# imp_rev1.net
KiCad netlist of a schematic drawn in EAGLE
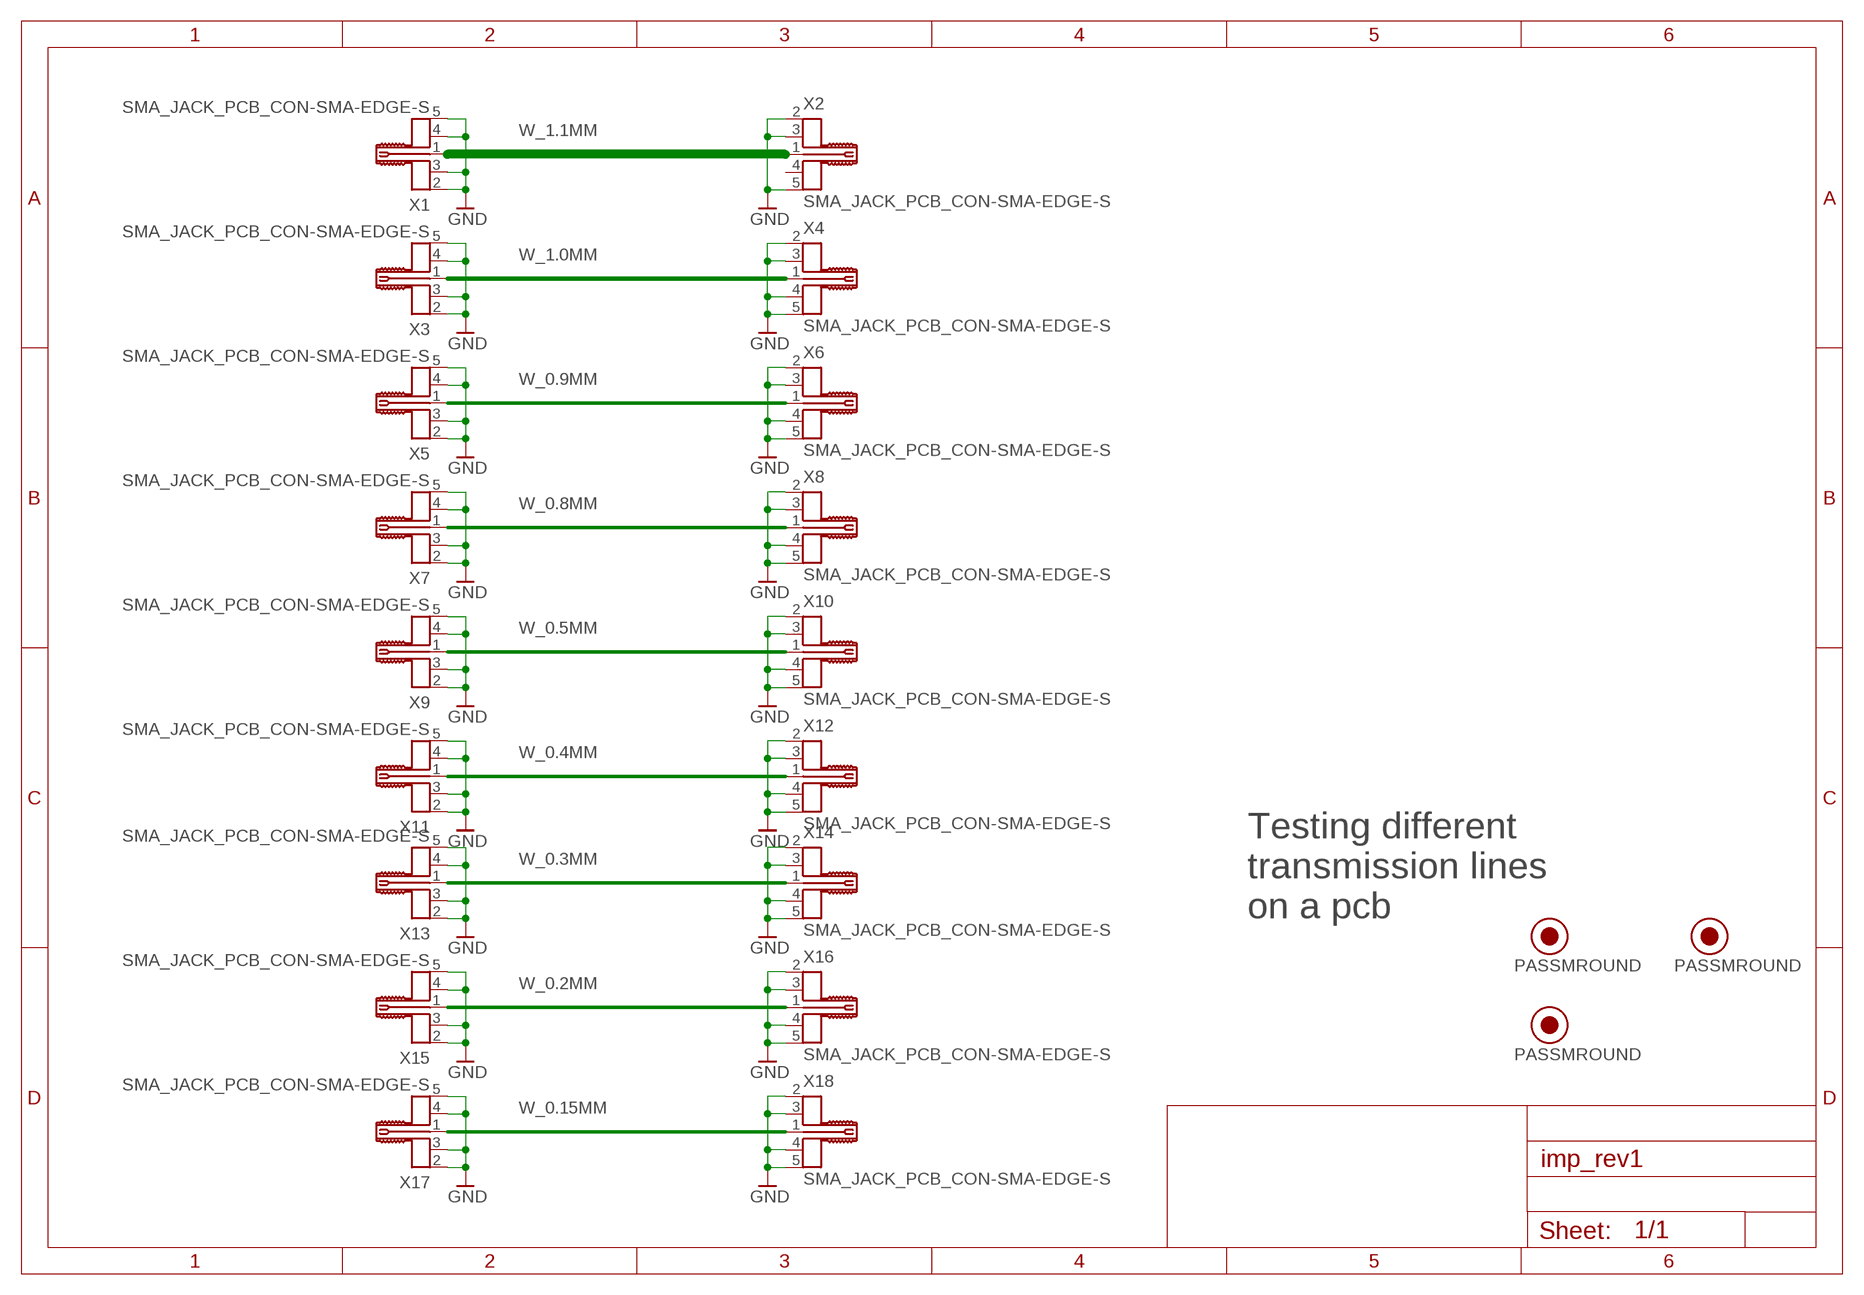
[diagram p0: schematic, sheet 1]

(export (version "E")
  (design (tool "Eeschema 10.0.6"))
  (components
    (comp (ref "P1")
      (value "PASSMROUND")
      (footprint "eagle-import:PASSM")
      (libsource (lib "eagle-import") (part "PASSMROUND"))
    )
    (comp (ref "P2")
      (value "PASSMROUND")
      (footprint "eagle-import:PASSM")
      (libsource (lib "eagle-import") (part "PASSMROUND"))
    )
    (comp (ref "P3")
      (value "PASSMROUND")
      (footprint "eagle-import:PASSM")
      (libsource (lib "eagle-import") (part "PASSMROUND"))
    )
    (comp (ref "X1")
      (value "SMA_JACK_PCB_CON-SMA-EDGE-S")
      (footprint "eagle-import:SMA_JACK_PCB_CON-SMA-EDGE-S")
      (libsource (lib "eagle-import") (part "SMA_JACK_PCB_CON-SMA-EDGE-S"))
    )
    (comp (ref "X2")
      (value "SMA_JACK_PCB_CON-SMA-EDGE-S")
      (footprint "eagle-import:SMA_JACK_PCB_CON-SMA-EDGE-S")
      (libsource (lib "eagle-import") (part "SMA_JACK_PCB_CON-SMA-EDGE-S"))
    )
    (comp (ref "X3")
      (value "SMA_JACK_PCB_CON-SMA-EDGE-S")
      (footprint "eagle-import:SMA_JACK_PCB_CON-SMA-EDGE-S")
      (libsource (lib "eagle-import") (part "SMA_JACK_PCB_CON-SMA-EDGE-S"))
    )
    (comp (ref "X4")
      (value "SMA_JACK_PCB_CON-SMA-EDGE-S")
      (footprint "eagle-import:SMA_JACK_PCB_CON-SMA-EDGE-S")
      (libsource (lib "eagle-import") (part "SMA_JACK_PCB_CON-SMA-EDGE-S"))
    )
    (comp (ref "X5")
      (value "SMA_JACK_PCB_CON-SMA-EDGE-S")
      (footprint "eagle-import:SMA_JACK_PCB_CON-SMA-EDGE-S")
      (libsource (lib "eagle-import") (part "SMA_JACK_PCB_CON-SMA-EDGE-S"))
    )
    (comp (ref "X6")
      (value "SMA_JACK_PCB_CON-SMA-EDGE-S")
      (footprint "eagle-import:SMA_JACK_PCB_CON-SMA-EDGE-S")
      (libsource (lib "eagle-import") (part "SMA_JACK_PCB_CON-SMA-EDGE-S"))
    )
    (comp (ref "X7")
      (value "SMA_JACK_PCB_CON-SMA-EDGE-S")
      (footprint "eagle-import:SMA_JACK_PCB_CON-SMA-EDGE-S")
      (libsource (lib "eagle-import") (part "SMA_JACK_PCB_CON-SMA-EDGE-S"))
    )
    (comp (ref "X8")
      (value "SMA_JACK_PCB_CON-SMA-EDGE-S")
      (footprint "eagle-import:SMA_JACK_PCB_CON-SMA-EDGE-S")
      (libsource (lib "eagle-import") (part "SMA_JACK_PCB_CON-SMA-EDGE-S"))
    )
    (comp (ref "X9")
      (value "SMA_JACK_PCB_CON-SMA-EDGE-S")
      (footprint "eagle-import:SMA_JACK_PCB_CON-SMA-EDGE-S")
      (libsource (lib "eagle-import") (part "SMA_JACK_PCB_CON-SMA-EDGE-S"))
    )
    (comp (ref "X10")
      (value "SMA_JACK_PCB_CON-SMA-EDGE-S")
      (footprint "eagle-import:SMA_JACK_PCB_CON-SMA-EDGE-S")
      (libsource (lib "eagle-import") (part "SMA_JACK_PCB_CON-SMA-EDGE-S"))
    )
    (comp (ref "X11")
      (value "SMA_JACK_PCB_CON-SMA-EDGE-S")
      (footprint "eagle-import:SMA_JACK_PCB_CON-SMA-EDGE-S")
      (libsource (lib "eagle-import") (part "SMA_JACK_PCB_CON-SMA-EDGE-S"))
    )
    (comp (ref "X12")
      (value "SMA_JACK_PCB_CON-SMA-EDGE-S")
      (footprint "eagle-import:SMA_JACK_PCB_CON-SMA-EDGE-S")
      (libsource (lib "eagle-import") (part "SMA_JACK_PCB_CON-SMA-EDGE-S"))
    )
    (comp (ref "X13")
      (value "SMA_JACK_PCB_CON-SMA-EDGE-S")
      (footprint "eagle-import:SMA_JACK_PCB_CON-SMA-EDGE-S")
      (libsource (lib "eagle-import") (part "SMA_JACK_PCB_CON-SMA-EDGE-S"))
    )
    (comp (ref "X14")
      (value "SMA_JACK_PCB_CON-SMA-EDGE-S")
      (footprint "eagle-import:SMA_JACK_PCB_CON-SMA-EDGE-S")
      (libsource (lib "eagle-import") (part "SMA_JACK_PCB_CON-SMA-EDGE-S"))
    )
    (comp (ref "X15")
      (value "SMA_JACK_PCB_CON-SMA-EDGE-S")
      (footprint "eagle-import:SMA_JACK_PCB_CON-SMA-EDGE-S")
      (libsource (lib "eagle-import") (part "SMA_JACK_PCB_CON-SMA-EDGE-S"))
    )
    (comp (ref "X16")
      (value "SMA_JACK_PCB_CON-SMA-EDGE-S")
      (footprint "eagle-import:SMA_JACK_PCB_CON-SMA-EDGE-S")
      (libsource (lib "eagle-import") (part "SMA_JACK_PCB_CON-SMA-EDGE-S"))
    )
    (comp (ref "X17")
      (value "SMA_JACK_PCB_CON-SMA-EDGE-S")
      (footprint "eagle-import:SMA_JACK_PCB_CON-SMA-EDGE-S")
      (libsource (lib "eagle-import") (part "SMA_JACK_PCB_CON-SMA-EDGE-S"))
    )
    (comp (ref "X18")
      (value "SMA_JACK_PCB_CON-SMA-EDGE-S")
      (footprint "eagle-import:SMA_JACK_PCB_CON-SMA-EDGE-S")
      (libsource (lib "eagle-import") (part "SMA_JACK_PCB_CON-SMA-EDGE-S"))
    )
  )
  (nets
    (net (code "1") (name "/W_0.2MM") (class "Default")
      (node (ref "X15") (pin "1") (pinfunction "1_1") (pintype "bidirectional"))
      (node (ref "X16") (pin "1") (pinfunction "1_1") (pintype "bidirectional"))
    )
    (net (code "2") (name "/W_0.3MM") (class "Default")
      (node (ref "X13") (pin "1") (pinfunction "1_1") (pintype "bidirectional"))
      (node (ref "X14") (pin "1") (pinfunction "1_1") (pintype "bidirectional"))
    )
    (net (code "3") (name "/W_0.4MM") (class "Default")
      (node (ref "X11") (pin "1") (pinfunction "1_1") (pintype "bidirectional"))
      (node (ref "X12") (pin "1") (pinfunction "1_1") (pintype "bidirectional"))
    )
    (net (code "4") (name "/W_0.5MM") (class "Default")
      (node (ref "X10") (pin "1") (pinfunction "1_1") (pintype "bidirectional"))
      (node (ref "X9") (pin "1") (pinfunction "1_1") (pintype "bidirectional"))
    )
    (net (code "5") (name "/W_0.8MM") (class "Default")
      (node (ref "X7") (pin "1") (pinfunction "1_1") (pintype "bidirectional"))
      (node (ref "X8") (pin "1") (pinfunction "1_1") (pintype "bidirectional"))
    )
    (net (code "6") (name "/W_0.9MM") (class "Default")
      (node (ref "X5") (pin "1") (pinfunction "1_1") (pintype "bidirectional"))
      (node (ref "X6") (pin "1") (pinfunction "1_1") (pintype "bidirectional"))
    )
    (net (code "7") (name "/W_0.15MM") (class "Default")
      (node (ref "X17") (pin "1") (pinfunction "1_1") (pintype "bidirectional"))
      (node (ref "X18") (pin "1") (pinfunction "1_1") (pintype "bidirectional"))
    )
    (net (code "8") (name "/W_1.0MM") (class "Default")
      (node (ref "X3") (pin "1") (pinfunction "1_1") (pintype "bidirectional"))
      (node (ref "X4") (pin "1") (pinfunction "1_1") (pintype "bidirectional"))
    )
    (net (code "9") (name "/W_1.1MM") (class "Default")
      (node (ref "X1") (pin "1") (pinfunction "1_1") (pintype "bidirectional"))
      (node (ref "X2") (pin "1") (pinfunction "1_1") (pintype "bidirectional"))
    )
    (net (code "10") (name "GND") (class "Default")
      (node (ref "X1") (pin "2") (pinfunction "GND1_2") (pintype "bidirectional"))
      (node (ref "X1") (pin "3") (pinfunction "GND2_3") (pintype "bidirectional"))
      (node (ref "X1") (pin "4") (pinfunction "GND3_4") (pintype "bidirectional"))
      (node (ref "X1") (pin "5") (pinfunction "GND4_5") (pintype "bidirectional"))
      (node (ref "X10") (pin "2") (pinfunction "GND1_2") (pintype "bidirectional"))
      (node (ref "X10") (pin "3") (pinfunction "GND2_3") (pintype "bidirectional"))
      (node (ref "X10") (pin "4") (pinfunction "GND3_4") (pintype "bidirectional"))
      (node (ref "X10") (pin "5") (pinfunction "GND4_5") (pintype "bidirectional"))
      (node (ref "X11") (pin "2") (pinfunction "GND1_2") (pintype "bidirectional"))
      (node (ref "X11") (pin "3") (pinfunction "GND2_3") (pintype "bidirectional"))
      (node (ref "X11") (pin "4") (pinfunction "GND3_4") (pintype "bidirectional"))
      (node (ref "X11") (pin "5") (pinfunction "GND4_5") (pintype "bidirectional"))
      (node (ref "X12") (pin "2") (pinfunction "GND1_2") (pintype "bidirectional"))
      (node (ref "X12") (pin "3") (pinfunction "GND2_3") (pintype "bidirectional"))
      (node (ref "X12") (pin "4") (pinfunction "GND3_4") (pintype "bidirectional"))
      (node (ref "X12") (pin "5") (pinfunction "GND4_5") (pintype "bidirectional"))
      (node (ref "X13") (pin "2") (pinfunction "GND1_2") (pintype "bidirectional"))
      (node (ref "X13") (pin "3") (pinfunction "GND2_3") (pintype "bidirectional"))
      (node (ref "X13") (pin "4") (pinfunction "GND3_4") (pintype "bidirectional"))
      (node (ref "X13") (pin "5") (pinfunction "GND4_5") (pintype "bidirectional"))
      (node (ref "X14") (pin "2") (pinfunction "GND1_2") (pintype "bidirectional"))
      (node (ref "X14") (pin "3") (pinfunction "GND2_3") (pintype "bidirectional"))
      (node (ref "X14") (pin "4") (pinfunction "GND3_4") (pintype "bidirectional"))
      (node (ref "X14") (pin "5") (pinfunction "GND4_5") (pintype "bidirectional"))
      (node (ref "X15") (pin "2") (pinfunction "GND1_2") (pintype "bidirectional"))
      (node (ref "X15") (pin "3") (pinfunction "GND2_3") (pintype "bidirectional"))
      (node (ref "X15") (pin "4") (pinfunction "GND3_4") (pintype "bidirectional"))
      (node (ref "X15") (pin "5") (pinfunction "GND4_5") (pintype "bidirectional"))
      (node (ref "X16") (pin "2") (pinfunction "GND1_2") (pintype "bidirectional"))
      (node (ref "X16") (pin "3") (pinfunction "GND2_3") (pintype "bidirectional"))
      (node (ref "X16") (pin "4") (pinfunction "GND3_4") (pintype "bidirectional"))
      (node (ref "X16") (pin "5") (pinfunction "GND4_5") (pintype "bidirectional"))
      (node (ref "X17") (pin "2") (pinfunction "GND1_2") (pintype "bidirectional"))
      (node (ref "X17") (pin "3") (pinfunction "GND2_3") (pintype "bidirectional"))
      (node (ref "X17") (pin "4") (pinfunction "GND3_4") (pintype "bidirectional"))
      (node (ref "X17") (pin "5") (pinfunction "GND4_5") (pintype "bidirectional"))
      (node (ref "X18") (pin "2") (pinfunction "GND1_2") (pintype "bidirectional"))
      (node (ref "X18") (pin "3") (pinfunction "GND2_3") (pintype "bidirectional"))
      (node (ref "X18") (pin "4") (pinfunction "GND3_4") (pintype "bidirectional"))
      (node (ref "X18") (pin "5") (pinfunction "GND4_5") (pintype "bidirectional"))
      (node (ref "X2") (pin "2") (pinfunction "GND1_2") (pintype "bidirectional"))
      (node (ref "X2") (pin "3") (pinfunction "GND2_3") (pintype "bidirectional"))
      (node (ref "X2") (pin "5") (pinfunction "GND4_5") (pintype "bidirectional"))
      (node (ref "X3") (pin "2") (pinfunction "GND1_2") (pintype "bidirectional"))
      (node (ref "X3") (pin "3") (pinfunction "GND2_3") (pintype "bidirectional"))
      (node (ref "X3") (pin "4") (pinfunction "GND3_4") (pintype "bidirectional"))
      (node (ref "X3") (pin "5") (pinfunction "GND4_5") (pintype "bidirectional"))
      (node (ref "X4") (pin "2") (pinfunction "GND1_2") (pintype "bidirectional"))
      (node (ref "X4") (pin "3") (pinfunction "GND2_3") (pintype "bidirectional"))
      (node (ref "X4") (pin "4") (pinfunction "GND3_4") (pintype "bidirectional"))
      (node (ref "X4") (pin "5") (pinfunction "GND4_5") (pintype "bidirectional"))
      (node (ref "X5") (pin "2") (pinfunction "GND1_2") (pintype "bidirectional"))
      (node (ref "X5") (pin "3") (pinfunction "GND2_3") (pintype "bidirectional"))
      (node (ref "X5") (pin "4") (pinfunction "GND3_4") (pintype "bidirectional"))
      (node (ref "X5") (pin "5") (pinfunction "GND4_5") (pintype "bidirectional"))
      (node (ref "X6") (pin "2") (pinfunction "GND1_2") (pintype "bidirectional"))
      (node (ref "X6") (pin "3") (pinfunction "GND2_3") (pintype "bidirectional"))
      (node (ref "X6") (pin "4") (pinfunction "GND3_4") (pintype "bidirectional"))
      (node (ref "X6") (pin "5") (pinfunction "GND4_5") (pintype "bidirectional"))
      (node (ref "X7") (pin "2") (pinfunction "GND1_2") (pintype "bidirectional"))
      (node (ref "X7") (pin "3") (pinfunction "GND2_3") (pintype "bidirectional"))
      (node (ref "X7") (pin "4") (pinfunction "GND3_4") (pintype "bidirectional"))
      (node (ref "X7") (pin "5") (pinfunction "GND4_5") (pintype "bidirectional"))
      (node (ref "X8") (pin "2") (pinfunction "GND1_2") (pintype "bidirectional"))
      (node (ref "X8") (pin "3") (pinfunction "GND2_3") (pintype "bidirectional"))
      (node (ref "X8") (pin "4") (pinfunction "GND3_4") (pintype "bidirectional"))
      (node (ref "X8") (pin "5") (pinfunction "GND4_5") (pintype "bidirectional"))
      (node (ref "X9") (pin "2") (pinfunction "GND1_2") (pintype "bidirectional"))
      (node (ref "X9") (pin "3") (pinfunction "GND2_3") (pintype "bidirectional"))
      (node (ref "X9") (pin "4") (pinfunction "GND3_4") (pintype "bidirectional"))
      (node (ref "X9") (pin "5") (pinfunction "GND4_5") (pintype "bidirectional"))
    )
    (net (code "11") (name "unconnected-(X2-GND3-Pad4)") (class "Default")
      (node (ref "X2") (pin "4") (pinfunction "GND3_4") (pintype "bidirectional"))
    )
  )
)
